# v1.net
KiCad netlist of a schematic drawn in EAGLE
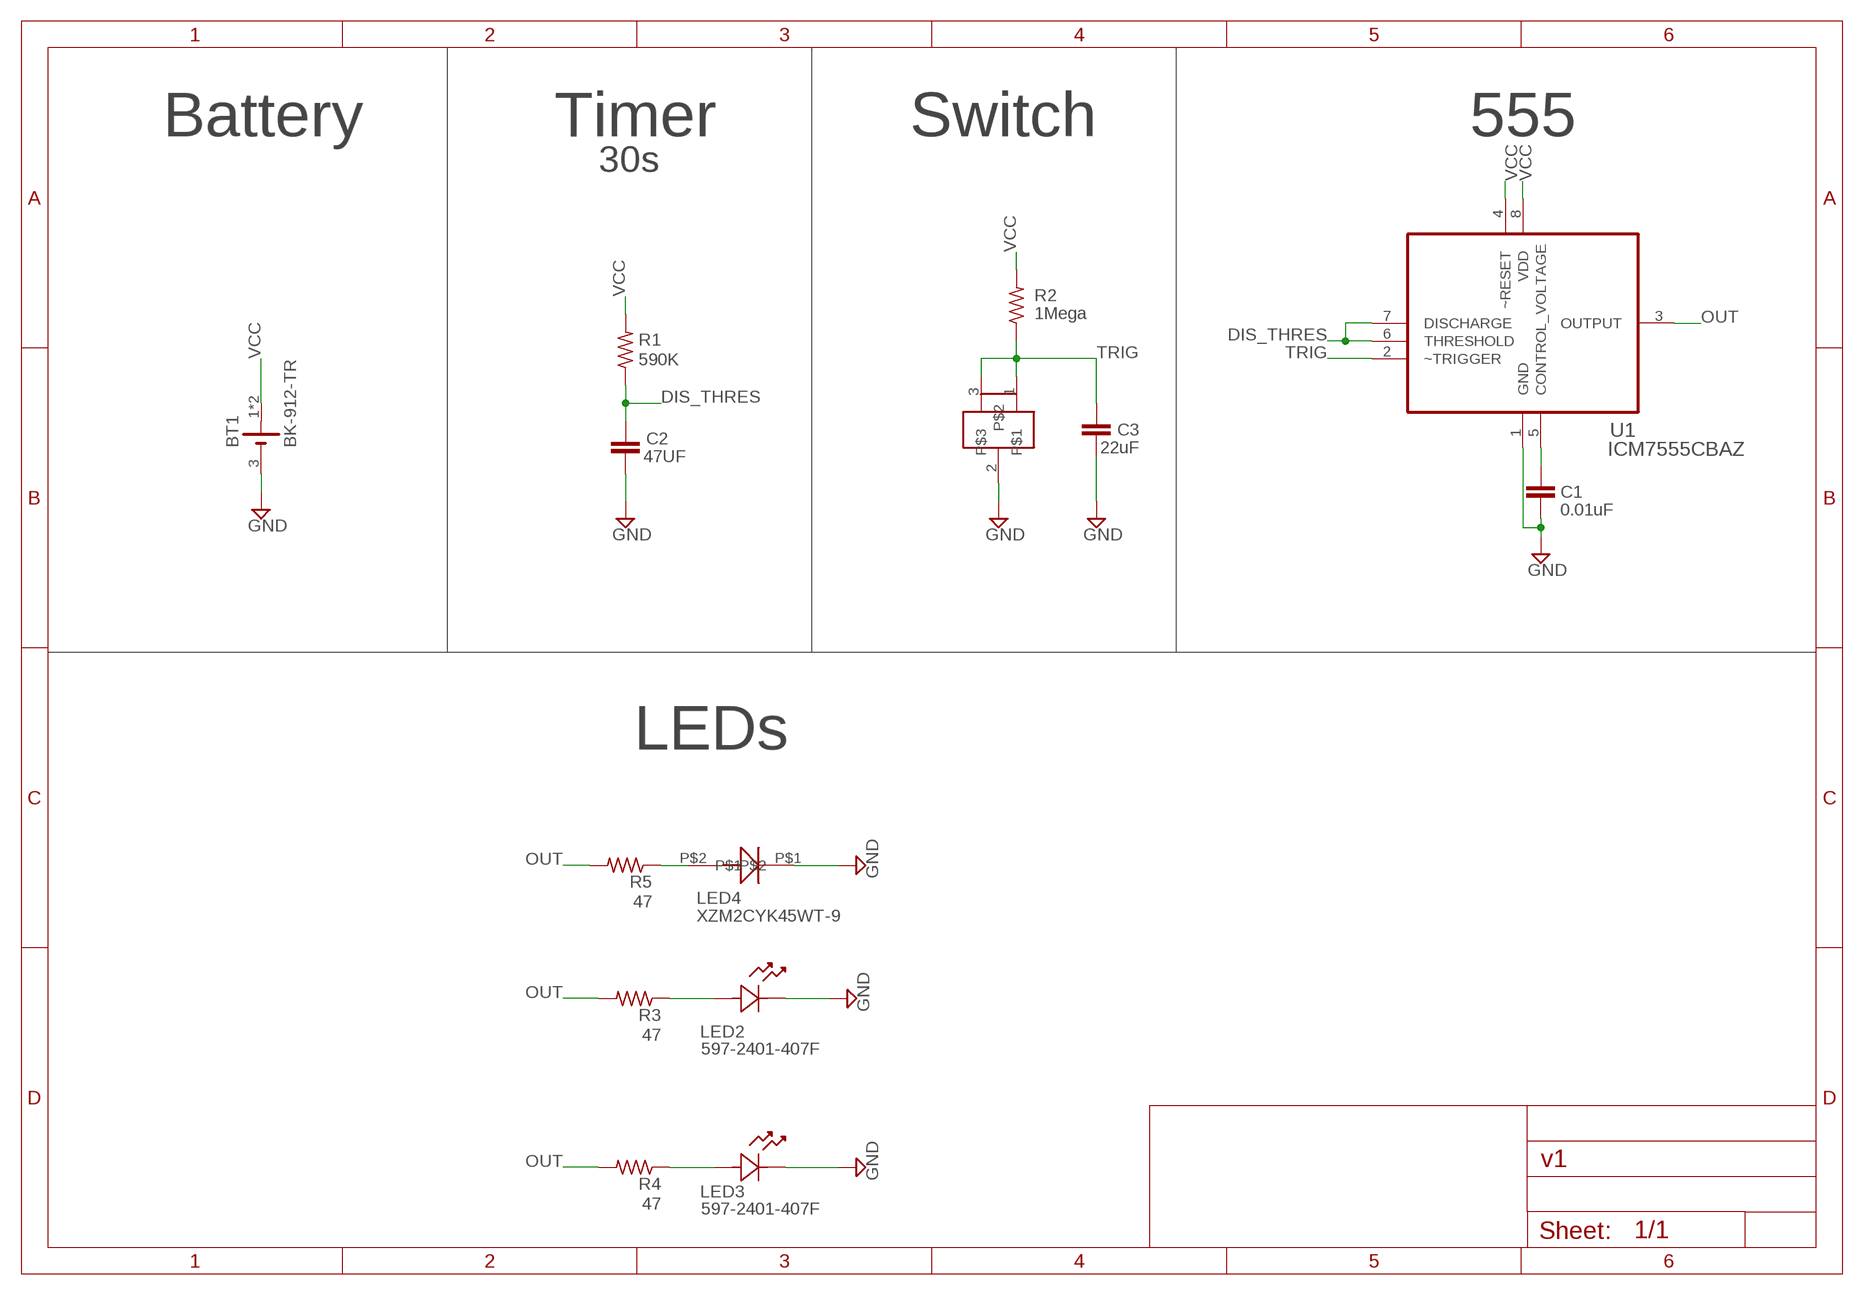
[diagram p0: schematic, sheet 1]

(export (version "E")
  (design (tool "Eeschema 10.0.6"))
  (components
    (comp (ref "BT1")
      (value "BK-912-TR")
      (footprint "eagle-import:MPD_BK-912-TR")
      (fields (field (name "MF") "MPD (Memory"))
      (libsource (lib "eagle-import") (part "BK-912-TR"))
    )
    (comp (ref "C1")
      (value "0.01uF")
      (footprint "eagle-import:C0603")
      (libsource (lib "eagle-import") (part "C-EUC0603"))
    )
    (comp (ref "C2")
      (value "47UF")
      (footprint "eagle-import:C0603")
      (libsource (lib "eagle-import") (part "C-EUC0603"))
    )
    (comp (ref "C3")
      (value "22uF")
      (footprint "eagle-import:C0603")
      (fields (field (name "MF") "Samsung") (field (name "MP") "CL10A226MQ8NRNE"))
      (libsource (lib "eagle-import") (part "C-EUC0603"))
    )
    (comp (ref "LED2")
      (value "597-2401-407F")
      (footprint "eagle-import:LED_597-2401-407F")
      (fields (field (name "MF") "Dialight"))
      (libsource (lib "eagle-import") (part "597-2401-407F"))
    )
    (comp (ref "LED3")
      (value "597-2401-407F")
      (footprint "eagle-import:LED_597-2401-407F")
      (fields (field (name "MF") "Dialight"))
      (libsource (lib "eagle-import") (part "597-2401-407F"))
    )
    (comp (ref "LED4")
      (value "XZM2CYK45WT-9")
      (footprint "eagle-import:XZM2CYK45WT")
      (libsource (lib "eagle-import") (part "XZM2CYK45WT-9"))
    )
    (comp (ref "R1")
      (value "590K")
      (footprint "eagle-import:R0603")
      (libsource (lib "eagle-import") (part "R-US_R0603"))
    )
    (comp (ref "R2")
      (value "1Mega")
      (footprint "eagle-import:R0603")
      (libsource (lib "eagle-import") (part "R-US_R0603"))
    )
    (comp (ref "R3")
      (value "47")
      (footprint "eagle-import:R0603")
      (fields (field (name "MF") "YAGEO"))
      (libsource (lib "eagle-import") (part "R-US_R0603"))
    )
    (comp (ref "R4")
      (value "47")
      (footprint "eagle-import:R0603")
      (fields (field (name "MF") "YAGEO"))
      (libsource (lib "eagle-import") (part "R-US_R0603"))
    )
    (comp (ref "R5")
      (value "47")
      (footprint "eagle-import:R0603")
      (fields (field (name "MF") "YAGEO"))
      (libsource (lib "eagle-import") (part "R-US_R0603"))
    )
    (comp (ref "SW1")
      (value "TM1000Q")
      (footprint "eagle-import:SIP750W46P254L1400H1010Q3")
      (libsource (lib "eagle-import") (part "TM1000Q"))
    )
    (comp (ref "U1")
      (value "ICM7555CBAZ")
      (footprint "eagle-import:SOIC127P600X175-8N")
      (fields (field (name "MF") "Renesas Electronics"))
      (libsource (lib "eagle-import") (part "ICM7555CBAZ"))
    )
  )
  (nets
    (net (code "1") (name "/DIS_THRES") (class "Default")
      (node (ref "C2") (pin "2") (pinfunction "2_2") (pintype "passive"))
      (node (ref "R1") (pin "1") (pinfunction "1_1") (pintype "passive"))
      (node (ref "U1") (pin "6") (pinfunction "THRESHOLD_6") (pintype "input"))
      (node (ref "U1") (pin "7") (pinfunction "DISCHARGE_7") (pintype "output"))
    )
    (net (code "2") (name "/OUT") (class "Default")
      (node (ref "R3") (pin "2") (pinfunction "2_2") (pintype "passive"))
      (node (ref "R4") (pin "2") (pinfunction "2_2") (pintype "passive"))
      (node (ref "R5") (pin "2") (pinfunction "2_2") (pintype "passive"))
      (node (ref "U1") (pin "3") (pinfunction "OUTPUT_3") (pintype "output"))
    )
    (net (code "3") (name "/TRIG") (class "Default")
      (node (ref "C3") (pin "2") (pinfunction "2_2") (pintype "passive"))
      (node (ref "R2") (pin "1") (pinfunction "1_1") (pintype "passive"))
      (node (ref "SW1") (pin "1") (pinfunction "P$1_1") (pintype "bidirectional"))
      (node (ref "SW1") (pin "3") (pinfunction "P$3_3") (pintype "bidirectional"))
      (node (ref "U1") (pin "2") (pinfunction "~{TRIGGER}_2") (pintype "input"))
    )
    (net (code "4") (name "/VCC") (class "Default")
      (node (ref "BT1") (pin "1") (pinfunction "+_1") (pintype "passive"))
      (node (ref "BT1") (pin "2") (pinfunction "+_2") (pintype "passive"))
      (node (ref "R1") (pin "2") (pinfunction "2_2") (pintype "passive"))
      (node (ref "R2") (pin "2") (pinfunction "2_2") (pintype "passive"))
      (node (ref "U1") (pin "4") (pinfunction "~{RESET}_4") (pintype "input"))
      (node (ref "U1") (pin "8") (pinfunction "VDD_8") (pintype "power_in"))
    )
    (net (code "5") (name "GND") (class "Default")
      (node (ref "BT1") (pin "3") (pinfunction "-_3") (pintype "passive"))
      (node (ref "C1") (pin "1") (pinfunction "1_1") (pintype "passive"))
      (node (ref "C2") (pin "1") (pinfunction "1_1") (pintype "passive"))
      (node (ref "C3") (pin "1") (pinfunction "1_1") (pintype "passive"))
      (node (ref "LED2") (pin "1") (pinfunction "1_1") (pintype "passive"))
      (node (ref "LED3") (pin "1") (pinfunction "1_1") (pintype "passive"))
      (node (ref "LED4") (pin "P$1") (pinfunction "P$1_P$1") (pintype "bidirectional"))
      (node (ref "SW1") (pin "2") (pinfunction "P$2_2") (pintype "bidirectional"))
      (node (ref "U1") (pin "1") (pinfunction "GND_1") (pintype "passive"))
    )
    (net (code "6") (name "Net-(LED2-Pad2)") (class "Default")
      (node (ref "LED2") (pin "2") (pinfunction "2_2") (pintype "passive"))
      (node (ref "R3") (pin "1") (pinfunction "1_1") (pintype "passive"))
    )
    (net (code "7") (name "Net-(LED3-Pad2)") (class "Default")
      (node (ref "LED3") (pin "2") (pinfunction "2_2") (pintype "passive"))
      (node (ref "R4") (pin "1") (pinfunction "1_1") (pintype "passive"))
    )
    (net (code "8") (name "Net-(LED4-PadP$2)") (class "Default")
      (node (ref "LED4") (pin "P$2") (pinfunction "P$2_P$2") (pintype "bidirectional"))
      (node (ref "R5") (pin "1") (pinfunction "1_1") (pintype "passive"))
    )
    (net (code "9") (name "Net-(U1-CONTROL_VOLTAGE)") (class "Default")
      (node (ref "C1") (pin "2") (pinfunction "2_2") (pintype "passive"))
      (node (ref "U1") (pin "5") (pinfunction "CONTROL_VOLTAGE_5") (pintype "input"))
    )
  )
)
